# usb2lds_v2_0.net
KiCad netlist of a schematic drawn in EAGLE
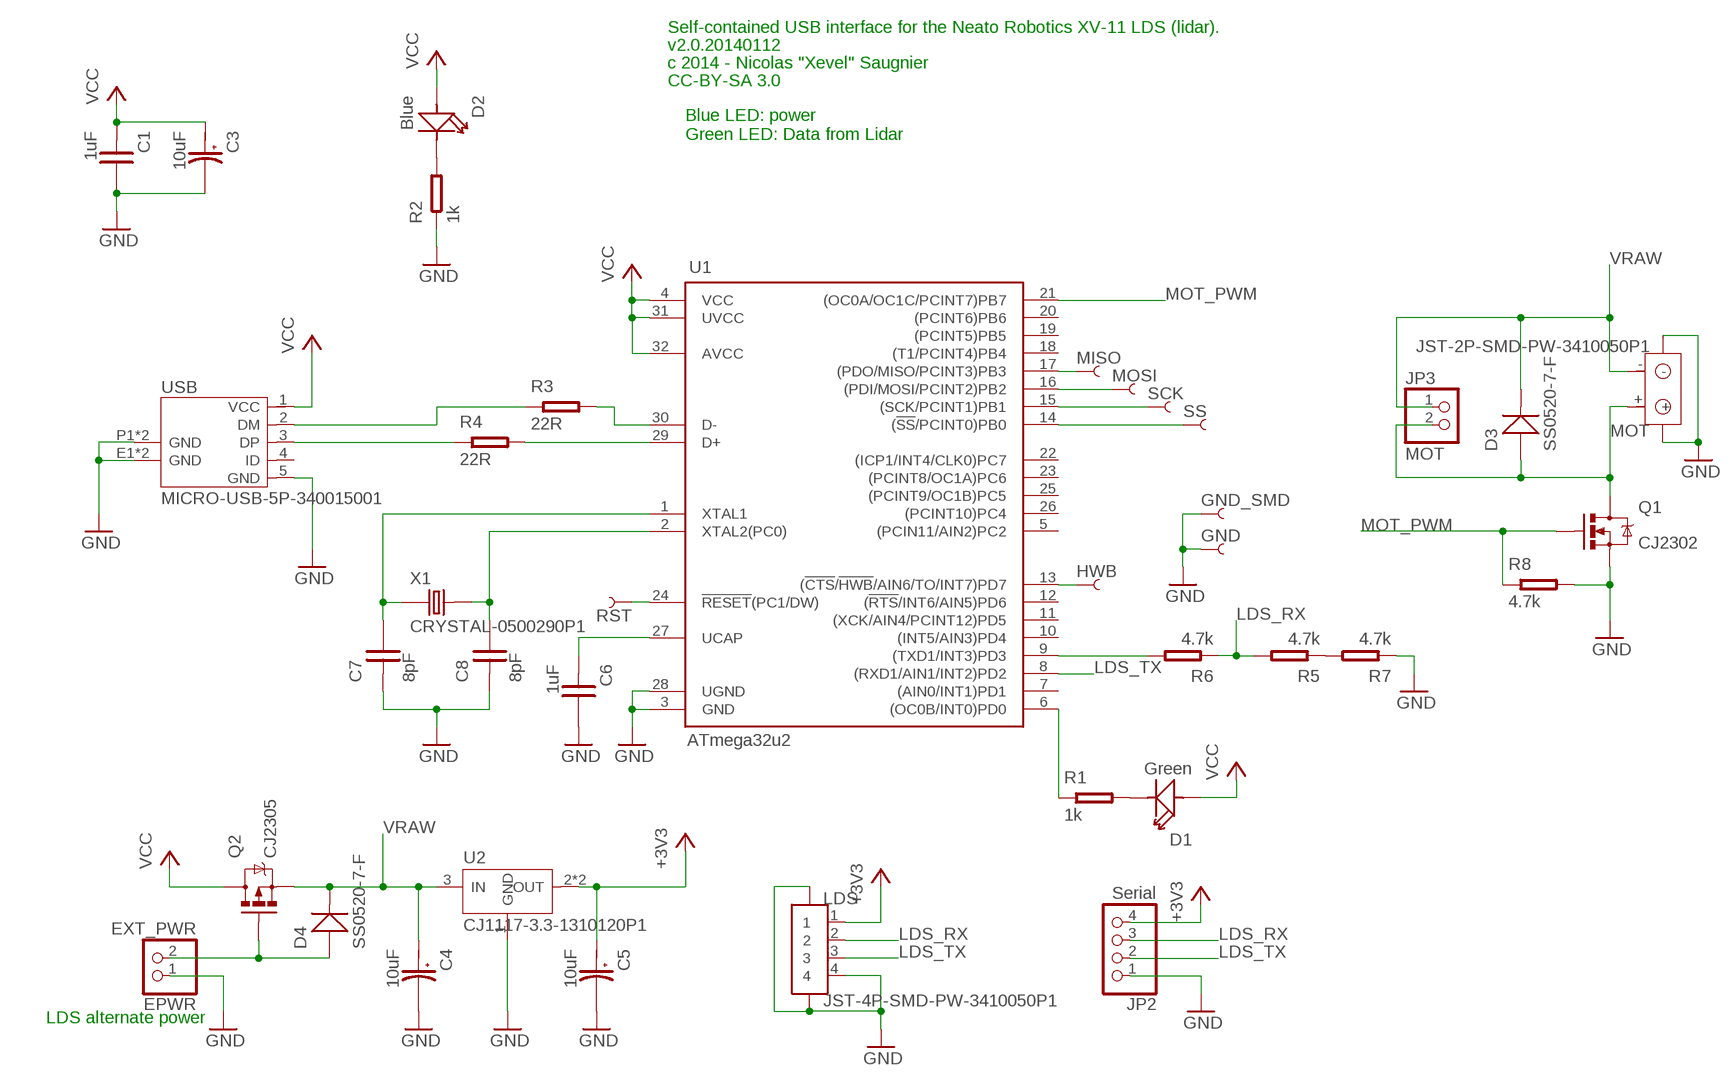
[diagram p0: schematic, sheet 1]

(export (version "E")
  (design (tool "Eeschema 10.0.6"))
  (components
    (comp (ref "C1")
      (value "1uF")
      (footprint "eagle-import:C0603")
      (libsource (lib "eagle-import") (part "C-0603"))
    )
    (comp (ref "C3")
      (value "10uF")
      (footprint "eagle-import:AVX-A")
      (libsource (lib "eagle-import") (part "C-POLAR-A"))
    )
    (comp (ref "C4")
      (value "10uF")
      (footprint "eagle-import:AVX-A")
      (libsource (lib "eagle-import") (part "C-POLAR-A"))
    )
    (comp (ref "C5")
      (value "10uF")
      (footprint "eagle-import:AVX-A")
      (libsource (lib "eagle-import") (part "C-POLAR-A"))
    )
    (comp (ref "C6")
      (value "1uF")
      (footprint "eagle-import:C0603")
      (libsource (lib "eagle-import") (part "C-0603"))
    )
    (comp (ref "C7")
      (value "8pF")
      (footprint "eagle-import:C0603")
      (libsource (lib "eagle-import") (part "C-0603"))
    )
    (comp (ref "C8")
      (value "8pF")
      (footprint "eagle-import:C0603")
      (libsource (lib "eagle-import") (part "C-0603"))
    )
    (comp (ref "D1")
      (value "Green")
      (footprint "eagle-import:LED0603")
      (libsource (lib "eagle-import") (part "LED"))
    )
    (comp (ref "D2")
      (value "Blue")
      (footprint "eagle-import:LED0603")
      (libsource (lib "eagle-import") (part "LED"))
    )
    (comp (ref "D3")
      (value "SS0520-7-F")
      (footprint "eagle-import:SOD123")
      (libsource (lib "eagle-import") (part "D-SOD-123"))
    )
    (comp (ref "D4")
      (value "SS0520-7-F")
      (footprint "eagle-import:SOD123")
      (libsource (lib "eagle-import") (part "D-SOD-123"))
    )
    (comp (ref "EPWR")
      (value "EXT_PWR")
      (footprint "eagle-import:1X02")
      (libsource (lib "eagle-import") (part "PINHD-1X2"))
    )
    (comp (ref "GND")
      (value "PIN_SMD_2X2.5")
      (footprint "eagle-import:PIN_SMD_2X2.5")
      (libsource (lib "eagle-import") (part "PIN_SMD_2X2.5"))
    )
    (comp (ref "GND_SMD")
      (value "PIN_SMD_2X2.5")
      (footprint "eagle-import:PIN_SMD_2X2.5")
      (libsource (lib "eagle-import") (part "PIN_SMD_2X2.5"))
    )
    (comp (ref "HWB")
      (value "PIN_SMD_2X2.5")
      (footprint "eagle-import:PIN_SMD_2X2.5")
      (libsource (lib "eagle-import") (part "PIN_SMD_2X2.5"))
    )
    (comp (ref "JP2")
      (value "Serial")
      (footprint "eagle-import:1X04")
      (libsource (lib "eagle-import") (part "PINHD-1X4"))
    )
    (comp (ref "JP3")
      (value "MOT")
      (footprint "eagle-import:1X02")
      (libsource (lib "eagle-import") (part "PINHD-1X2"))
    )
    (comp (ref "LDS")
      (value "JST-4P-SMD-PW-3410050P1")
      (footprint "eagle-import:CON-4P-SMD-2.0-90D")
      (libsource (lib "eagle-import") (part "JST-4P-SMD-PW-3410050P1"))
    )
    (comp (ref "MISO")
      (value "PIN_SMD_2X2.5")
      (footprint "eagle-import:PIN_SMD_2X2.5")
      (libsource (lib "eagle-import") (part "PIN_SMD_2X2.5"))
    )
    (comp (ref "MOSI")
      (value "PIN_SMD_2X2.5")
      (footprint "eagle-import:PIN_SMD_2X2.5")
      (libsource (lib "eagle-import") (part "PIN_SMD_2X2.5"))
    )
    (comp (ref "MOT")
      (value "JST-2P-SMD-PW-3410050P1")
      (footprint "eagle-import:2P-SMD-2.0-90D")
      (libsource (lib "eagle-import") (part "JST-2P-SMD-PW-3410050P1"))
    )
    (comp (ref "Q1")
      (value "CJ2302")
      (footprint "eagle-import:SOT-23-3_N_SSOT-3_N")
      (libsource (lib "eagle-import") (part "MOSFET_N_SOT23-3"))
    )
    (comp (ref "Q2")
      (value "CJ2305")
      (footprint "eagle-import:SOT-23-3_N_SSOT-3_N")
      (libsource (lib "eagle-import") (part "MOSFET_P_FDN308P"))
    )
    (comp (ref "R1")
      (value "1k")
      (footprint "eagle-import:R0603")
      (libsource (lib "eagle-import") (part "R-0603"))
    )
    (comp (ref "R2")
      (value "1k")
      (footprint "eagle-import:R0603")
      (libsource (lib "eagle-import") (part "R-0603"))
    )
    (comp (ref "R3")
      (value "22R")
      (footprint "eagle-import:R0603")
      (libsource (lib "eagle-import") (part "R-0603"))
    )
    (comp (ref "R4")
      (value "22R")
      (footprint "eagle-import:R0603")
      (libsource (lib "eagle-import") (part "R-0603"))
    )
    (comp (ref "R5")
      (value "4.7k")
      (footprint "eagle-import:R0603")
      (libsource (lib "eagle-import") (part "R-0603"))
    )
    (comp (ref "R6")
      (value "4.7k")
      (footprint "eagle-import:R0603")
      (libsource (lib "eagle-import") (part "R-0603"))
    )
    (comp (ref "R7")
      (value "4.7k")
      (footprint "eagle-import:R0603")
      (libsource (lib "eagle-import") (part "R-0603"))
    )
    (comp (ref "R8")
      (value "4.7k")
      (footprint "eagle-import:R0603")
      (libsource (lib "eagle-import") (part "R-0603"))
    )
    (comp (ref "RST")
      (value "PIN_SMD_2X2.5")
      (footprint "eagle-import:PIN_SMD_2X2.5")
      (libsource (lib "eagle-import") (part "PIN_SMD_2X2.5"))
    )
    (comp (ref "SCK")
      (value "PIN_SMD_2X2.5")
      (footprint "eagle-import:PIN_SMD_2X2.5")
      (libsource (lib "eagle-import") (part "PIN_SMD_2X2.5"))
    )
    (comp (ref "SS")
      (value "PIN_SMD_2X2.5")
      (footprint "eagle-import:PIN_SMD_2X2.5")
      (libsource (lib "eagle-import") (part "PIN_SMD_2X2.5"))
    )
    (comp (ref "U1")
      (value "ATmega32u2")
      (footprint "eagle-import:QFN-32_50P_L_MOD")
      (libsource (lib "eagle-import") (part "IC_ATMEGAXXU2-MU_L_MOD"))
    )
    (comp (ref "U2")
      (value "CJ1117-3.3-1310120P1")
      (footprint "eagle-import:SOT89")
      (libsource (lib "eagle-import") (part "CJ1117-3.3-1310120P1"))
    )
    (comp (ref "USB")
      (value "MICRO-USB-5P-340015001")
      (footprint "eagle-import:B-SMD-5P")
      (libsource (lib "eagle-import") (part "MICRO-USB-5P-340015001"))
    )
    (comp (ref "X1")
      (value "CRYSTAL-0500290P1")
      (footprint "eagle-import:2P-SMD-5.0X3.2")
      (libsource (lib "eagle-import") (part "CRYSTAL-0500290P1"))
    )
  )
  (nets
    (net (code "1") (name "+3V3") (class "Default")
      (node (ref "C5") (pin "+") (pinfunction "1_+") (pintype "bidirectional"))
      (node (ref "JP2") (pin "4") (pinfunction "4_4") (pintype "passive"))
      (node (ref "LDS") (pin "1") (pinfunction "1_1") (pintype "bidirectional"))
      (node (ref "U2") (pin "2") (pinfunction "OUT_2") (pintype "bidirectional"))
      (node (ref "U2") (pin "4") (pinfunction "OUT_4") (pintype "bidirectional"))
    )
    (net (code "2") (name "/LDS_RX") (class "Default")
      (node (ref "JP2") (pin "3") (pinfunction "3_3") (pintype "passive"))
      (node (ref "LDS") (pin "2") (pinfunction "2_2") (pintype "bidirectional"))
      (node (ref "R5") (pin "2") (pinfunction "2_2") (pintype "passive"))
      (node (ref "R6") (pin "1") (pinfunction "1_1") (pintype "passive"))
    )
    (net (code "3") (name "/LDS_TX") (class "Default")
      (node (ref "JP2") (pin "2") (pinfunction "2_2") (pintype "passive"))
      (node (ref "LDS") (pin "3") (pinfunction "3_3") (pintype "bidirectional"))
      (node (ref "U1") (pin "8") (pinfunction "(RXD1/AIN1/INT2)PD2_8") (pintype "bidirectional"))
    )
    (net (code "4") (name "/MOT_PWM") (class "Default")
      (node (ref "Q1") (pin "1") (pinfunction "G_1") (pintype "passive"))
      (node (ref "R8") (pin "1") (pinfunction "1_1") (pintype "passive"))
      (node (ref "U1") (pin "21") (pinfunction "(OC0A/OC1C/PCINT7)PB7_21") (pintype "bidirectional"))
    )
    (net (code "5") (name "/VRAW") (class "Default")
      (node (ref "C4") (pin "+") (pinfunction "1_+") (pintype "bidirectional"))
      (node (ref "D3") (pin "-") (pinfunction "-_-") (pintype "passive"))
      (node (ref "D4") (pin "-") (pinfunction "-_-") (pintype "passive"))
      (node (ref "JP3") (pin "1") (pinfunction "1_1") (pintype "passive"))
      (node (ref "MOT") (pin "-") (pinfunction "-_-") (pintype "bidirectional"))
      (node (ref "Q2") (pin "2") (pinfunction "S_2") (pintype "passive"))
      (node (ref "U2") (pin "3") (pinfunction "IN_3") (pintype "bidirectional"))
    )
    (net (code "6") (name "GND") (class "Default")
      (node (ref "C1") (pin "2") (pinfunction "2_2") (pintype "passive"))
      (node (ref "C3") (pin "-") (pinfunction "2_-") (pintype "bidirectional"))
      (node (ref "C4") (pin "-") (pinfunction "2_-") (pintype "bidirectional"))
      (node (ref "C5") (pin "-") (pinfunction "2_-") (pintype "bidirectional"))
      (node (ref "C6") (pin "2") (pinfunction "2_2") (pintype "passive"))
      (node (ref "C7") (pin "1") (pinfunction "1_1") (pintype "passive"))
      (node (ref "C8") (pin "1") (pinfunction "1_1") (pintype "passive"))
      (node (ref "EPWR") (pin "1") (pinfunction "1_1") (pintype "passive"))
      (node (ref "GND") (pin "PIN") (pinfunction "1_PIN") (pintype "bidirectional"))
      (node (ref "GND_SMD") (pin "PIN") (pinfunction "1_PIN") (pintype "bidirectional"))
      (node (ref "JP2") (pin "1") (pinfunction "1_1") (pintype "passive"))
      (node (ref "LDS") (pin "4") (pinfunction "4_4") (pintype "bidirectional"))
      (node (ref "LDS") (pin "5") (pinfunction "5_5") (pintype "bidirectional"))
      (node (ref "LDS") (pin "6") (pinfunction "6_6") (pintype "bidirectional"))
      (node (ref "MOT") (pin "3") (pinfunction "3_3") (pintype "bidirectional"))
      (node (ref "MOT") (pin "4") (pinfunction "4_4") (pintype "bidirectional"))
      (node (ref "Q1") (pin "2") (pinfunction "S_2") (pintype "passive"))
      (node (ref "R2") (pin "1") (pinfunction "1_1") (pintype "passive"))
      (node (ref "R7") (pin "1") (pinfunction "1_1") (pintype "passive"))
      (node (ref "R8") (pin "2") (pinfunction "2_2") (pintype "passive"))
      (node (ref "U1") (pin "28") (pinfunction "UGND_28") (pintype "power_in"))
      (node (ref "U1") (pin "3") (pinfunction "GND_3") (pintype "power_in"))
      (node (ref "U2") (pin "1") (pinfunction "GND_1") (pintype "bidirectional"))
      (node (ref "USB") (pin "5") (pinfunction "GND_5") (pintype "bidirectional"))
      (node (ref "USB") (pin "E1") (pinfunction "GND_E1") (pintype "bidirectional"))
      (node (ref "USB") (pin "E2") (pinfunction "GND_E2") (pintype "bidirectional"))
      (node (ref "USB") (pin "P1") (pinfunction "GND_P1") (pintype "bidirectional"))
      (node (ref "USB") (pin "P2") (pinfunction "GND_P2") (pintype "bidirectional"))
    )
    (net (code "7") (name "Net-(D1-Pad-)") (class "Default")
      (node (ref "D1") (pin "-") (pinfunction "-_-") (pintype "passive"))
      (node (ref "R1") (pin "2") (pinfunction "2_2") (pintype "passive"))
    )
    (net (code "8") (name "Net-(D2-Pad-)") (class "Default")
      (node (ref "D2") (pin "-") (pinfunction "-_-") (pintype "passive"))
      (node (ref "R2") (pin "2") (pinfunction "2_2") (pintype "passive"))
    )
    (net (code "9") (name "Net-(HWB-1)") (class "Default")
      (node (ref "HWB") (pin "PIN") (pinfunction "1_PIN") (pintype "bidirectional"))
      (node (ref "U1") (pin "13") (pinfunction "(~{CTS}/~{HWB}/AIN6/TO/INT7)PD7_13") (pintype "bidirectional"))
    )
    (net (code "10") (name "Net-(MISO-1)") (class "Default")
      (node (ref "MISO") (pin "PIN") (pinfunction "1_PIN") (pintype "bidirectional"))
      (node (ref "U1") (pin "17") (pinfunction "(PDO/MISO/PCINT3)PB3_17") (pintype "bidirectional"))
    )
    (net (code "11") (name "Net-(MOSI-1)") (class "Default")
      (node (ref "MOSI") (pin "PIN") (pinfunction "1_PIN") (pintype "bidirectional"))
      (node (ref "U1") (pin "16") (pinfunction "(PDI/MOSI/PCINT2)PB2_16") (pintype "bidirectional"))
    )
    (net (code "12") (name "Net-(Q1-D)") (class "Default")
      (node (ref "D3") (pin "+") (pinfunction "+_+") (pintype "passive"))
      (node (ref "JP3") (pin "2") (pinfunction "2_2") (pintype "passive"))
      (node (ref "MOT") (pin "+") (pinfunction "+_+") (pintype "bidirectional"))
      (node (ref "Q1") (pin "3") (pinfunction "D_3") (pintype "passive"))
    )
    (net (code "13") (name "Net-(Q2-G)") (class "Default")
      (node (ref "D4") (pin "+") (pinfunction "+_+") (pintype "passive"))
      (node (ref "EPWR") (pin "2") (pinfunction "2_2") (pintype "passive"))
      (node (ref "Q2") (pin "1") (pinfunction "G_1") (pintype "passive"))
    )
    (net (code "14") (name "Net-(R5-Pad1)") (class "Default")
      (node (ref "R5") (pin "1") (pinfunction "1_1") (pintype "passive"))
      (node (ref "R7") (pin "2") (pinfunction "2_2") (pintype "passive"))
    )
    (net (code "15") (name "Net-(RST-1)") (class "Default")
      (node (ref "RST") (pin "PIN") (pinfunction "1_PIN") (pintype "bidirectional"))
      (node (ref "U1") (pin "24") (pinfunction "~{RESET}(PC1/DW)_24") (pintype "bidirectional"))
    )
    (net (code "16") (name "Net-(SCK-1)") (class "Default")
      (node (ref "SCK") (pin "PIN") (pinfunction "1_PIN") (pintype "bidirectional"))
      (node (ref "U1") (pin "15") (pinfunction "(SCK/PCINT1)PB1_15") (pintype "bidirectional"))
    )
    (net (code "17") (name "Net-(SS-1)") (class "Default")
      (node (ref "SS") (pin "PIN") (pinfunction "1_PIN") (pintype "bidirectional"))
      (node (ref "U1") (pin "14") (pinfunction "(~{SS}/PCINT0)PB0_14") (pintype "bidirectional"))
    )
    (net (code "18") (name "Net-(U1-(OC0B{slash}INT0)PD0)") (class "Default")
      (node (ref "R1") (pin "1") (pinfunction "1_1") (pintype "passive"))
      (node (ref "U1") (pin "6") (pinfunction "(OC0B/INT0)PD0_6") (pintype "bidirectional"))
    )
    (net (code "19") (name "Net-(U1-(TXD1{slash}INT3)PD3)") (class "Default")
      (node (ref "R6") (pin "2") (pinfunction "2_2") (pintype "passive"))
      (node (ref "U1") (pin "9") (pinfunction "(TXD1/INT3)PD3_9") (pintype "bidirectional"))
    )
    (net (code "20") (name "Net-(U1-D+)") (class "Default")
      (node (ref "R4") (pin "2") (pinfunction "2_2") (pintype "passive"))
      (node (ref "U1") (pin "29") (pinfunction "D+_29") (pintype "bidirectional"))
    )
    (net (code "21") (name "Net-(U1-D-)") (class "Default")
      (node (ref "R3") (pin "2") (pinfunction "2_2") (pintype "passive"))
      (node (ref "U1") (pin "30") (pinfunction "D-_30") (pintype "bidirectional"))
    )
    (net (code "22") (name "Net-(U1-UCAP)") (class "Default")
      (node (ref "C6") (pin "1") (pinfunction "1_1") (pintype "passive"))
      (node (ref "U1") (pin "27") (pinfunction "UCAP_27") (pintype "passive"))
    )
    (net (code "23") (name "Net-(U1-XTAL1)") (class "Default")
      (node (ref "C7") (pin "2") (pinfunction "2_2") (pintype "passive"))
      (node (ref "U1") (pin "1") (pinfunction "XTAL1_1") (pintype "bidirectional"))
      (node (ref "X1") (pin "1") (pinfunction "1_1") (pintype "passive"))
    )
    (net (code "24") (name "Net-(U1-XTAL2(PC0))") (class "Default")
      (node (ref "C8") (pin "2") (pinfunction "2_2") (pintype "passive"))
      (node (ref "U1") (pin "2") (pinfunction "XTAL2(PC0)_2") (pintype "bidirectional"))
      (node (ref "X1") (pin "2") (pinfunction "2_2") (pintype "passive"))
    )
    (net (code "25") (name "Net-(USB-DM)") (class "Default")
      (node (ref "R3") (pin "1") (pinfunction "1_1") (pintype "passive"))
      (node (ref "USB") (pin "2") (pinfunction "DM_2") (pintype "bidirectional"))
    )
    (net (code "26") (name "Net-(USB-DP)") (class "Default")
      (node (ref "R4") (pin "1") (pinfunction "1_1") (pintype "passive"))
      (node (ref "USB") (pin "3") (pinfunction "DP_3") (pintype "bidirectional"))
    )
    (net (code "27") (name "VCC") (class "Default")
      (node (ref "C1") (pin "1") (pinfunction "1_1") (pintype "passive"))
      (node (ref "C3") (pin "+") (pinfunction "1_+") (pintype "bidirectional"))
      (node (ref "D1") (pin "+") (pinfunction "+_+") (pintype "passive"))
      (node (ref "D2") (pin "+") (pinfunction "+_+") (pintype "passive"))
      (node (ref "Q2") (pin "3") (pinfunction "D_3") (pintype "passive"))
      (node (ref "U1") (pin "31") (pinfunction "UVCC_31") (pintype "power_in"))
      (node (ref "U1") (pin "32") (pinfunction "AVCC_32") (pintype "power_in"))
      (node (ref "U1") (pin "4") (pinfunction "VCC_4") (pintype "power_in"))
      (node (ref "USB") (pin "1") (pinfunction "VCC_1") (pintype "bidirectional"))
    )
    (net (code "28") (name "unconnected-(U1-(AIN0{slash}INT1)PD1-Pad7)") (class "Default")
      (node (ref "U1") (pin "7") (pinfunction "(AIN0/INT1)PD1_7") (pintype "bidirectional"))
    )
    (net (code "29") (name "unconnected-(U1-(ICP1{slash}INT4{slash}CLK0)PC7-Pad22)") (class "Default")
      (node (ref "U1") (pin "22") (pinfunction "(ICP1/INT4/CLK0)PC7_22") (pintype "bidirectional"))
    )
    (net (code "30") (name "unconnected-(U1-(INT5{slash}AIN3)PD4-Pad10)") (class "Default")
      (node (ref "U1") (pin "10") (pinfunction "(INT5/AIN3)PD4_10") (pintype "bidirectional"))
    )
    (net (code "31") (name "unconnected-(U1-(PCIN11{slash}AIN2)PC2-Pad5)") (class "Default")
      (node (ref "U1") (pin "5") (pinfunction "(PCIN11/AIN2)PC2_5") (pintype "bidirectional"))
    )
    (net (code "32") (name "unconnected-(U1-(PCINT5)PB5-Pad19)") (class "Default")
      (node (ref "U1") (pin "19") (pinfunction "(PCINT5)PB5_19") (pintype "bidirectional"))
    )
    (net (code "33") (name "unconnected-(U1-(PCINT6)PB6-Pad20)") (class "Default")
      (node (ref "U1") (pin "20") (pinfunction "(PCINT6)PB6_20") (pintype "bidirectional"))
    )
    (net (code "34") (name "unconnected-(U1-(PCINT8{slash}OC1A)PC6-Pad23)") (class "Default")
      (node (ref "U1") (pin "23") (pinfunction "(PCINT8/OC1A)PC6_23") (pintype "bidirectional"))
    )
    (net (code "35") (name "unconnected-(U1-(PCINT9{slash}OC1B)PC5-Pad25)") (class "Default")
      (node (ref "U1") (pin "25") (pinfunction "(PCINT9/OC1B)PC5_25") (pintype "bidirectional"))
    )
    (net (code "36") (name "unconnected-(U1-(PCINT10)PC4-Pad26)") (class "Default")
      (node (ref "U1") (pin "26") (pinfunction "(PCINT10)PC4_26") (pintype "bidirectional"))
    )
    (net (code "37") (name "unconnected-(U1-(T1{slash}PCINT4)PB4-Pad18)") (class "Default")
      (node (ref "U1") (pin "18") (pinfunction "(T1/PCINT4)PB4_18") (pintype "bidirectional"))
    )
    (net (code "38") (name "unconnected-(U1-(XCK{slash}AIN4{slash}PCINT12)PD5-Pad11)") (class "Default")
      (node (ref "U1") (pin "11") (pinfunction "(XCK/AIN4/PCINT12)PD5_11") (pintype "bidirectional"))
    )
    (net (code "39") (name "unconnected-(U1-(~{RTS}{slash}INT6{slash}AIN5)PD6-Pad12)") (class "Default")
      (node (ref "U1") (pin "12") (pinfunction "(~{RTS}/INT6/AIN5)PD6_12") (pintype "bidirectional"))
    )
    (net (code "40") (name "unconnected-(USB-ID-Pad4)") (class "Default")
      (node (ref "USB") (pin "4") (pinfunction "ID_4") (pintype "bidirectional"))
    )
  )
)
